# c3_hw_1.net
KiCad netlist of a schematic drawn in Altium Designer
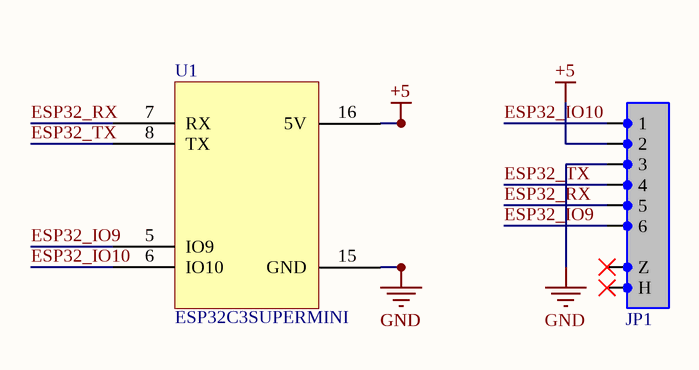
[diagram p0: c3_hw_1.SchDoc]

(export (version "E")
  (design (tool "Eeschema 10.0.6"))
  (components
    (comp (ref "JP1")
      (value "HDR-1X6")
      (footprint "HDR2.54-LI-6P")
      (description "6P接插件")
      (fields (field (name "版权归属") "源创客"))
      (libsource (lib "14.6-接插件-脚距2.54") (part "Header 6"))
    )
    (comp (ref "U1")
      (value "ESP32C3SUPERMINI")
      (footprint "ESP32C3SUPERMINI")
      (libsource (lib "userLib") (part "ESP32C3SUPERMINI"))
    )
  )
  (nets
    (net (code "1") (name "+5") (class "Default")
      (node (ref "JP1") (pin "2") (pinfunction "2_2") (pintype "passive"))
      (node (ref "U1") (pin "16") (pinfunction "5V_16") (pintype "passive"))
    )
    (net (code "2") (name "/ESP32_IO9") (class "Default")
      (node (ref "JP1") (pin "6") (pinfunction "6_6") (pintype "passive"))
      (node (ref "U1") (pin "5") (pinfunction "IO9_5") (pintype "passive"))
    )
    (net (code "3") (name "/ESP32_IO10") (class "Default")
      (node (ref "JP1") (pin "1") (pinfunction "1_1") (pintype "passive"))
      (node (ref "U1") (pin "6") (pinfunction "IO10_6") (pintype "passive"))
    )
    (net (code "4") (name "/ESP32_RX") (class "Default")
      (node (ref "JP1") (pin "5") (pinfunction "5_5") (pintype "passive"))
      (node (ref "U1") (pin "7") (pinfunction "RX_7") (pintype "passive"))
    )
    (net (code "5") (name "/ESP32_TX") (class "Default")
      (node (ref "JP1") (pin "4") (pinfunction "4_4") (pintype "passive"))
      (node (ref "U1") (pin "8") (pinfunction "TX_8") (pintype "passive"))
    )
    (net (code "6") (name "GND") (class "Default")
      (node (ref "JP1") (pin "3") (pinfunction "3_3") (pintype "passive"))
      (node (ref "U1") (pin "15") (pinfunction "GND_15") (pintype "passive"))
    )
    (net (code "7") (name "unconnected-(JP1-H-Pad100)") (class "Default")
      (node (ref "JP1") (pin "100") (pinfunction "H_100") (pintype "passive+no_connect"))
    )
    (net (code "8") (name "unconnected-(JP1-Z-Pad0)") (class "Default")
      (node (ref "JP1") (pin "0") (pinfunction "Z_0") (pintype "passive+no_connect"))
    )
  )
)
